# SchranklichtV3.net
KiCad netlist of a schematic drawn in EAGLE
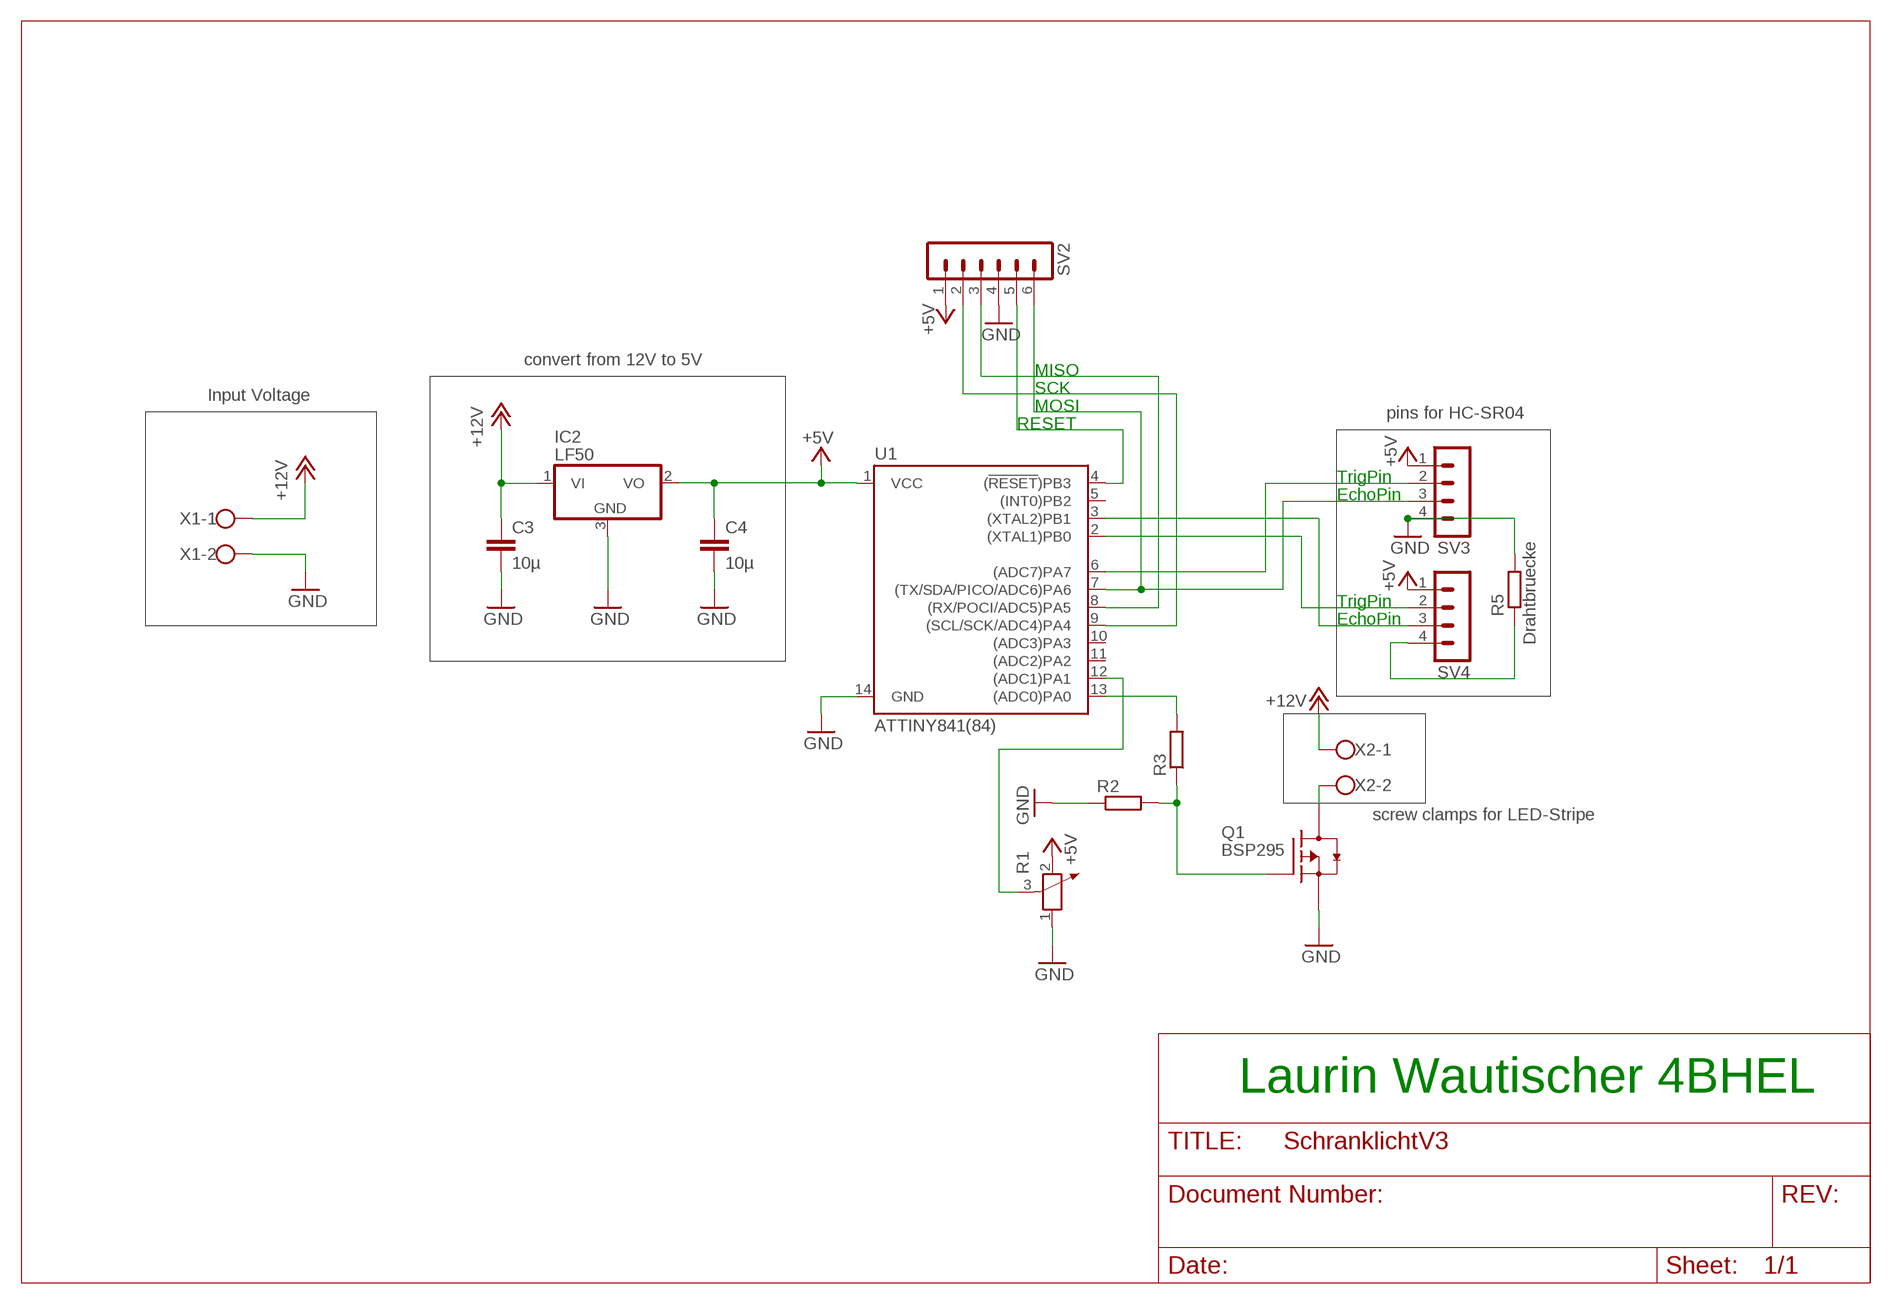
[diagram p0: schematic, sheet 1]

(export (version "E")
  (design (tool "Eeschema 10.0.6"))
  (components
    (comp (ref "C3")
      (value "10µ")
      (footprint "eagle-import:C1210")
      (libsource (lib "eagle-import") (part "C-EUC1210"))
    )
    (comp (ref "C4")
      (value "10µ")
      (footprint "eagle-import:C1210")
      (libsource (lib "eagle-import") (part "C-EUC1210"))
    )
    (comp (ref "IC2")
      (value "LF50")
      (footprint "eagle-import:TO252")
      (fields (field (name "SPICEPREFIX") "J"))
      (libsource (lib "eagle-import") (part "78DT05"))
    )
    (comp (ref "Q1")
      (value "BSP295")
      (footprint "eagle-import:SOT230P700X160-4N")
      (libsource (lib "eagle-import") (part "MOSFET-PCH_SOT-223"))
    )
    (comp (ref "R1")
      (value "POTENTIOMETER_PT-10")
      (footprint "eagle-import:PT-10")
      (libsource (lib "eagle-import") (part "POTENTIOMETER_PT-10"))
    )
    (comp (ref "R2")
      (value "R-EU_0207/10")
      (footprint "eagle-import:0207_10")
      (libsource (lib "eagle-import") (part "R-EU_0207/10"))
    )
    (comp (ref "R3")
      (value "R-EU_0207/10")
      (footprint "eagle-import:0207_10")
      (libsource (lib "eagle-import") (part "R-EU_0207/10"))
    )
    (comp (ref "R5")
      (value "Drahtbruecke")
      (footprint "eagle-import:0207_7")
      (libsource (lib "eagle-import") (part "R-EU_0207/7"))
    )
    (comp (ref "SV2")
      (value "MA06-1")
      (footprint "eagle-import:MA06-1")
      (libsource (lib "eagle-import") (part "MA06-1"))
    )
    (comp (ref "SV3")
      (value "MA04-1")
      (footprint "eagle-import:MA04-1")
      (libsource (lib "eagle-import") (part "MA04-1"))
    )
    (comp (ref "SV4")
      (value "MA04-1")
      (footprint "eagle-import:MA04-1")
      (libsource (lib "eagle-import") (part "MA04-1"))
    )
    (comp (ref "U1")
      (value "ATTINY841(84)")
      (footprint "eagle-import:SO14")
      (libsource (lib "eagle-import") (part "ATTINY84"))
    )
    (comp (ref "X1")
      (value "W237-102")
      (footprint "eagle-import:W237-102")
      (fields (field (name "MPN") "237-102"))
      (libsource (lib "eagle-import") (part "W237-102"))
    )
    (comp (ref "X2")
      (value "W237-102")
      (footprint "eagle-import:W237-102")
      (fields (field (name "MPN") "237-102"))
      (libsource (lib "eagle-import") (part "W237-102"))
    )
  )
  (nets
    (net (code "1") (name "+5V") (class "Default")
      (node (ref "C4") (pin "1") (pinfunction "1_1") (pintype "passive"))
      (node (ref "IC2") (pin "2") (pinfunction "VO_2") (pintype "passive"))
      (node (ref "R1") (pin "2") (pinfunction "2_2") (pintype "passive"))
      (node (ref "SV2") (pin "1") (pinfunction "1_1") (pintype "passive"))
      (node (ref "SV3") (pin "1") (pinfunction "1_1") (pintype "passive"))
      (node (ref "SV4") (pin "1") (pinfunction "1_1") (pintype "passive"))
      (node (ref "U1") (pin "1") (pinfunction "VCC_1") (pintype "bidirectional"))
    )
    (net (code "2") (name "+12V") (class "Default")
      (node (ref "C3") (pin "1") (pinfunction "1_1") (pintype "passive"))
      (node (ref "IC2") (pin "1") (pinfunction "VI_1") (pintype "input"))
      (node (ref "X1") (pin "1") (pinfunction "KL_1") (pintype "passive"))
      (node (ref "X2") (pin "1") (pinfunction "KL_1") (pintype "passive"))
    )
    (net (code "3") (name "GND") (class "Default")
      (node (ref "C3") (pin "2") (pinfunction "2_2") (pintype "passive"))
      (node (ref "C4") (pin "2") (pinfunction "2_2") (pintype "passive"))
      (node (ref "IC2") (pin "3") (pinfunction "GND_3") (pintype "passive"))
      (node (ref "Q1") (pin "3") (pinfunction "S_3") (pintype "passive"))
      (node (ref "R1") (pin "1") (pinfunction "1_1") (pintype "passive"))
      (node (ref "R2") (pin "1") (pinfunction "1_1") (pintype "passive"))
      (node (ref "R5") (pin "2") (pinfunction "2_2") (pintype "passive"))
      (node (ref "SV2") (pin "4") (pinfunction "4_4") (pintype "passive"))
      (node (ref "SV3") (pin "4") (pinfunction "4_4") (pintype "passive"))
      (node (ref "U1") (pin "14") (pinfunction "GND_14") (pintype "bidirectional"))
      (node (ref "X1") (pin "2") (pinfunction "KL_2") (pintype "passive"))
    )
    (net (code "4") (name "Net-(Q1-D)") (class "Default")
      (node (ref "Q1") (pin "4") (pinfunction "D_4") (pintype "passive"))
      (node (ref "X2") (pin "2") (pinfunction "KL_2") (pintype "passive"))
    )
    (net (code "5") (name "Net-(Q1-G)") (class "Default")
      (node (ref "Q1") (pin "1") (pinfunction "G_1") (pintype "passive"))
      (node (ref "R2") (pin "2") (pinfunction "2_2") (pintype "passive"))
      (node (ref "R3") (pin "1") (pinfunction "1_1") (pintype "passive"))
    )
    (net (code "6") (name "Net-(R5-Pad1)") (class "Default")
      (node (ref "R5") (pin "1") (pinfunction "1_1") (pintype "passive"))
      (node (ref "SV4") (pin "4") (pinfunction "4_4") (pintype "passive"))
    )
    (net (code "7") (name "Net-(U1-(ADC0)PA0)") (class "Default")
      (node (ref "R3") (pin "2") (pinfunction "2_2") (pintype "passive"))
      (node (ref "U1") (pin "13") (pinfunction "(ADC0)PA0_13") (pintype "bidirectional"))
    )
    (net (code "8") (name "Net-(U1-(ADC1)PA1)") (class "Default")
      (node (ref "R1") (pin "3") (pinfunction "3_3") (pintype "passive"))
      (node (ref "U1") (pin "12") (pinfunction "(ADC1)PA1_12") (pintype "bidirectional"))
    )
    (net (code "9") (name "Net-(U1-(ADC7)PA7)") (class "Default")
      (node (ref "SV3") (pin "2") (pinfunction "2_2") (pintype "passive"))
      (node (ref "U1") (pin "6") (pinfunction "(ADC7)PA7_6") (pintype "bidirectional"))
    )
    (net (code "10") (name "Net-(U1-(RX{slash}POCI{slash}ADC5)PA5)") (class "Default")
      (node (ref "SV2") (pin "3") (pinfunction "3_3") (pintype "passive"))
      (node (ref "U1") (pin "8") (pinfunction "(RX/POCI/ADC5)PA5_8") (pintype "bidirectional"))
    )
    (net (code "11") (name "Net-(U1-(SCL{slash}SCK{slash}ADC4)PA4)") (class "Default")
      (node (ref "SV2") (pin "2") (pinfunction "2_2") (pintype "passive"))
      (node (ref "U1") (pin "9") (pinfunction "(SCL/SCK/ADC4)PA4_9") (pintype "bidirectional"))
    )
    (net (code "12") (name "Net-(U1-(TX{slash}SDA{slash}PICO{slash}ADC6)PA6)") (class "Default")
      (node (ref "SV2") (pin "6") (pinfunction "6_6") (pintype "passive"))
      (node (ref "SV3") (pin "3") (pinfunction "3_3") (pintype "passive"))
      (node (ref "U1") (pin "7") (pinfunction "(TX/SDA/PICO/ADC6)PA6_7") (pintype "bidirectional"))
    )
    (net (code "13") (name "Net-(U1-(XTAL1)PB0)") (class "Default")
      (node (ref "SV4") (pin "2") (pinfunction "2_2") (pintype "passive"))
      (node (ref "U1") (pin "2") (pinfunction "(XTAL1)PB0_2") (pintype "bidirectional"))
    )
    (net (code "14") (name "Net-(U1-(XTAL2)PB1)") (class "Default")
      (node (ref "SV4") (pin "3") (pinfunction "3_3") (pintype "passive"))
      (node (ref "U1") (pin "3") (pinfunction "(XTAL2)PB1_3") (pintype "bidirectional"))
    )
    (net (code "15") (name "Net-(U1-(~{RESET})PB3)") (class "Default")
      (node (ref "SV2") (pin "5") (pinfunction "5_5") (pintype "passive"))
      (node (ref "U1") (pin "4") (pinfunction "(~{RESET})PB3_4") (pintype "bidirectional"))
    )
    (net (code "16") (name "unconnected-(U1-(ADC2)PA2-Pad11)") (class "Default")
      (node (ref "U1") (pin "11") (pinfunction "(ADC2)PA2_11") (pintype "bidirectional"))
    )
    (net (code "17") (name "unconnected-(U1-(ADC3)PA3-Pad10)") (class "Default")
      (node (ref "U1") (pin "10") (pinfunction "(ADC3)PA3_10") (pintype "bidirectional"))
    )
    (net (code "18") (name "unconnected-(U1-(INT0)PB2-Pad5)") (class "Default")
      (node (ref "U1") (pin "5") (pinfunction "(INT0)PB2_5") (pintype "bidirectional"))
    )
  )
)
